# NewBee.net
KiCad netlist of a schematic drawn in Altium Designer
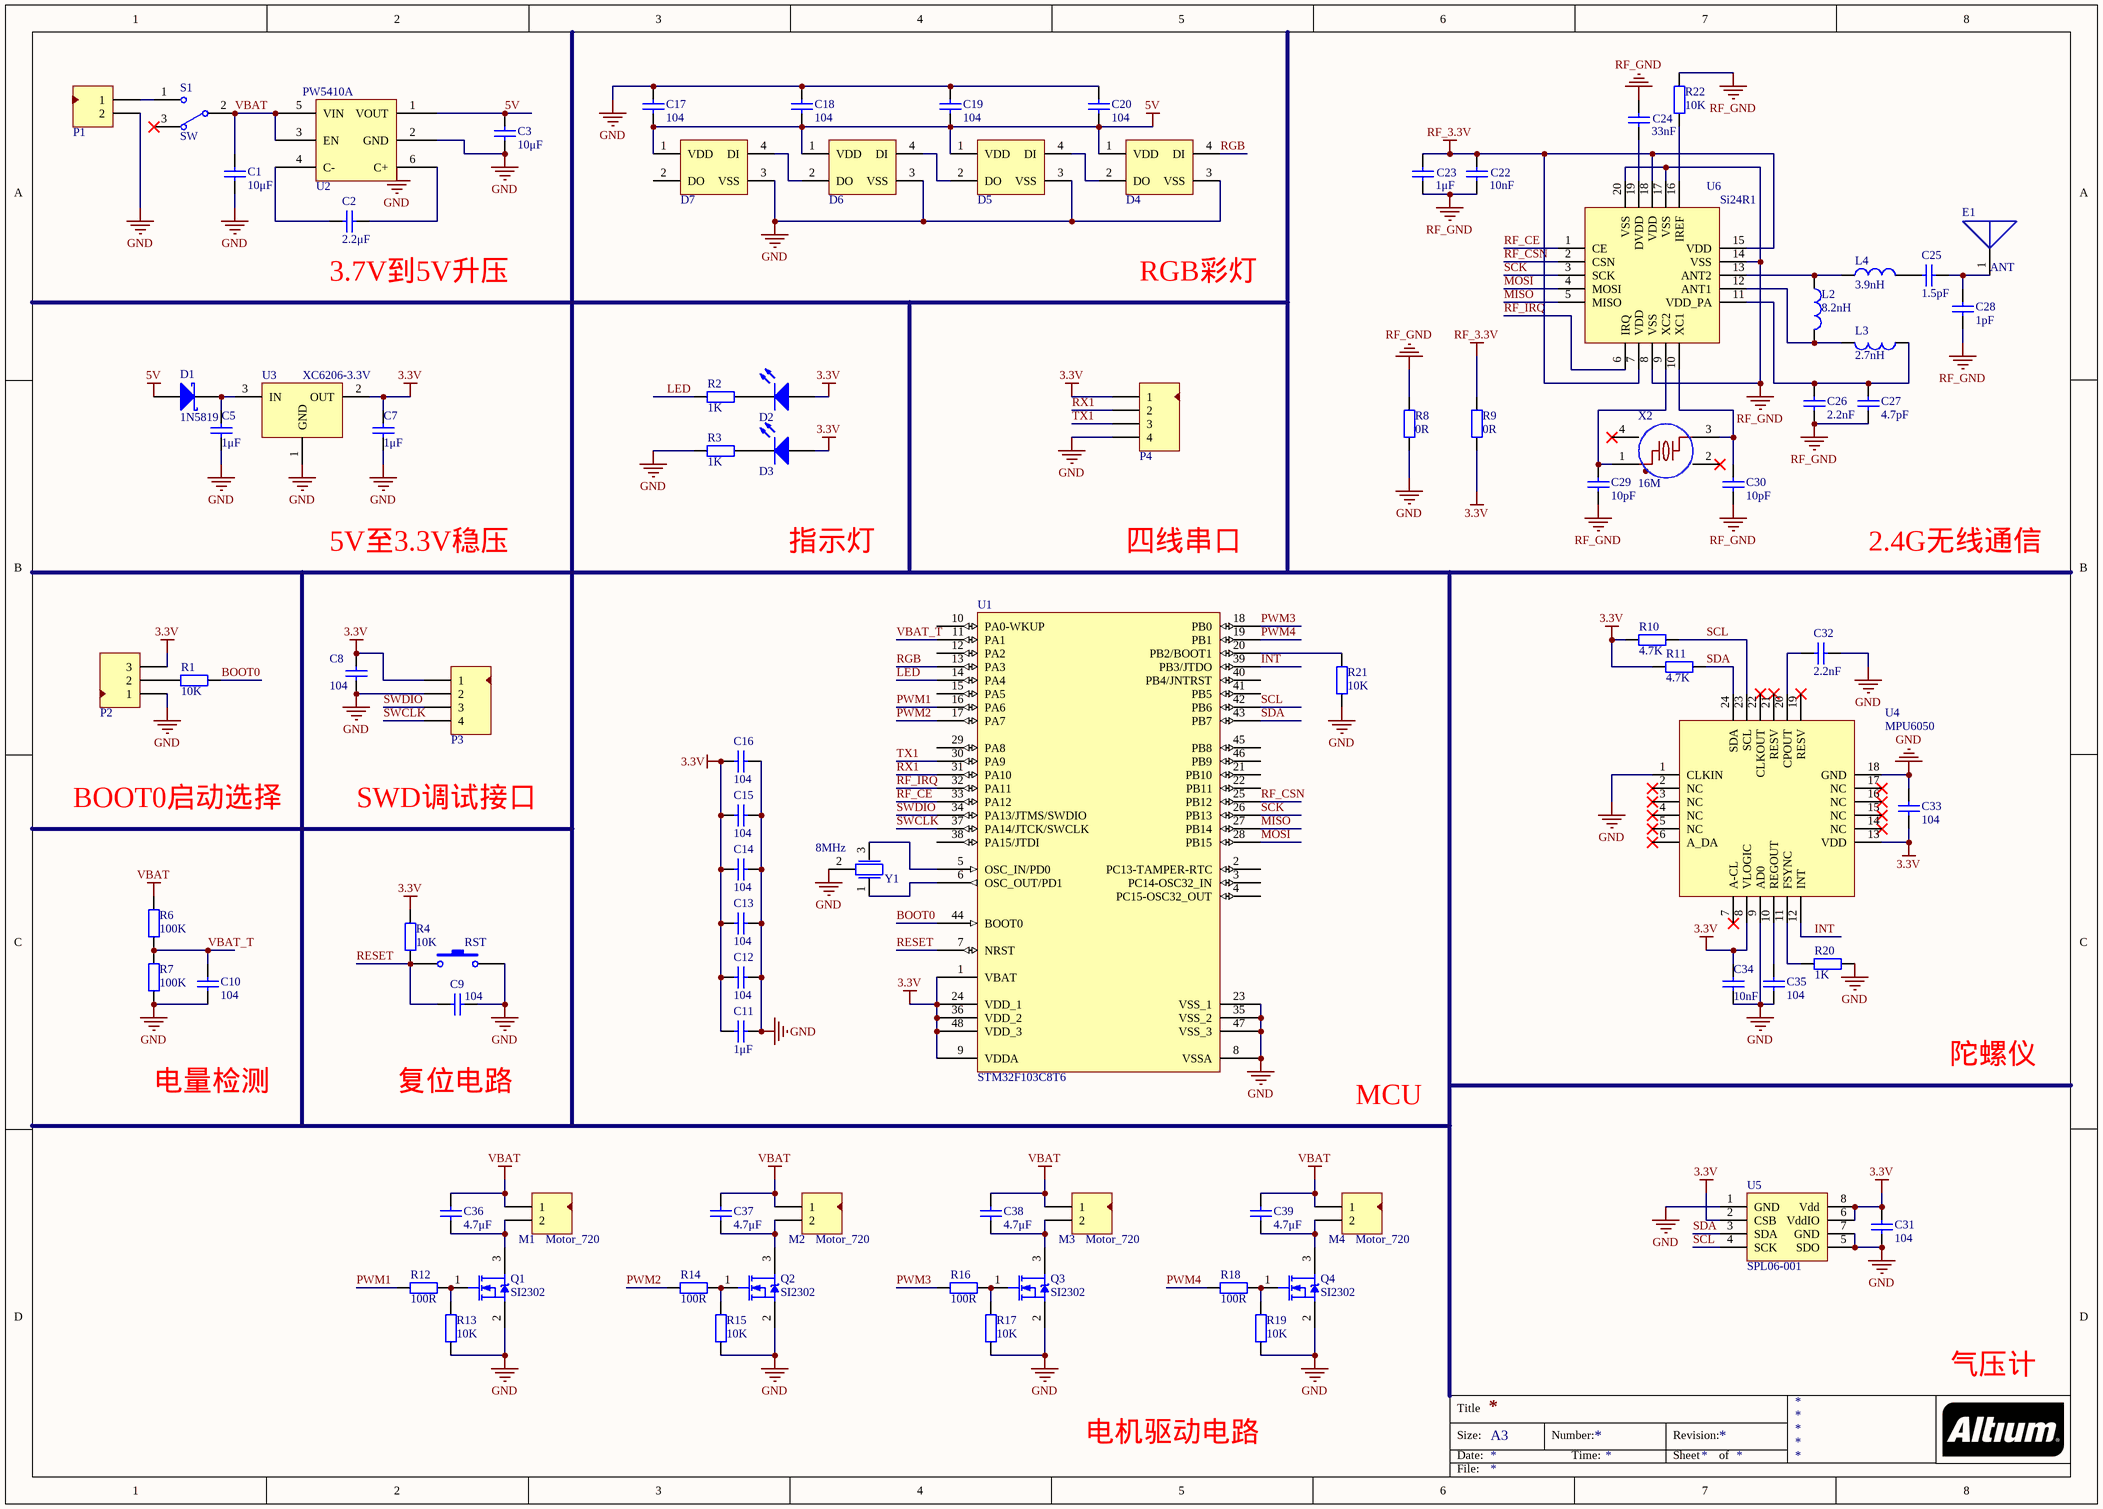
[diagram p0: NewBee.SchDoc]

(export (version "E")
  (design (tool "Eeschema 10.0.6"))
  (components
    (comp (ref "C1")
      (value "10μF")
      (footprint "C-0603")
      (description "贴片瓷片电容")
      (fields (field (name "PUBLISHER") "Altium Limited"))
      (libsource (lib "ChunLee") (part "Cap-S"))
    )
    (comp (ref "C2")
      (value "2.2μF")
      (footprint "C-0603")
      (description "贴片瓷片电容")
      (fields (field (name "PUBLISHER") "Altium Limited"))
      (libsource (lib "ChunLee") (part "Cap-S"))
    )
    (comp (ref "C3")
      (value "10μF")
      (footprint "C-0603")
      (description "贴片瓷片电容")
      (fields (field (name "PUBLISHER") "Altium Limited"))
      (libsource (lib "ChunLee") (part "Cap-S"))
    )
    (comp (ref "C5")
      (value "1μF")
      (footprint "C-0603")
      (description "贴片瓷片电容")
      (fields (field (name "PUBLISHER") "Altium Limited"))
      (libsource (lib "ChunLee") (part "Cap-S"))
    )
    (comp (ref "C7")
      (value "1μF")
      (footprint "C-0603")
      (description "贴片瓷片电容")
      (fields (field (name "PUBLISHER") "Altium Limited"))
      (libsource (lib "ChunLee") (part "Cap-S"))
    )
    (comp (ref "C8")
      (value "104")
      (footprint "C-0603")
      (description "贴片瓷片电容")
      (fields (field (name "PUBLISHER") "Altium Limited"))
      (libsource (lib "ChunLee") (part "Cap-S"))
    )
    (comp (ref "C9")
      (value "104")
      (footprint "C-0603")
      (description "贴片瓷片电容")
      (fields (field (name "PUBLISHER") "Altium Limited"))
      (libsource (lib "ChunLee") (part "Cap-S"))
    )
    (comp (ref "C10")
      (value "104")
      (footprint "C-0603")
      (description "贴片瓷片电容")
      (fields (field (name "PUBLISHER") "Altium Limited"))
      (libsource (lib "ChunLee") (part "Cap-S"))
    )
    (comp (ref "C11")
      (value "1μF")
      (footprint "C-0603")
      (description "贴片瓷片电容")
      (fields (field (name "PUBLISHER") "Altium Limited"))
      (libsource (lib "ChunLee") (part "Cap-S"))
    )
    (comp (ref "C12")
      (value "104")
      (footprint "C-0603")
      (description "贴片瓷片电容")
      (fields (field (name "PUBLISHER") "Altium Limited"))
      (libsource (lib "ChunLee") (part "Cap-S"))
    )
    (comp (ref "C13")
      (value "104")
      (footprint "C-0603")
      (description "贴片瓷片电容")
      (fields (field (name "PUBLISHER") "Altium Limited"))
      (libsource (lib "ChunLee") (part "Cap-S"))
    )
    (comp (ref "C14")
      (value "104")
      (footprint "C-0603")
      (description "贴片瓷片电容")
      (fields (field (name "PUBLISHER") "Altium Limited"))
      (libsource (lib "ChunLee") (part "Cap-S"))
    )
    (comp (ref "C15")
      (value "104")
      (footprint "C-0603")
      (description "贴片瓷片电容")
      (fields (field (name "PUBLISHER") "Altium Limited"))
      (libsource (lib "ChunLee") (part "Cap-S"))
    )
    (comp (ref "C16")
      (value "104")
      (footprint "C-0603")
      (description "贴片瓷片电容")
      (fields (field (name "PUBLISHER") "Altium Limited"))
      (libsource (lib "ChunLee") (part "Cap-S"))
    )
    (comp (ref "C17")
      (value "104")
      (footprint "C-0603")
      (description "贴片瓷片电容")
      (fields (field (name "PUBLISHER") "Altium Limited"))
      (libsource (lib "ChunLee") (part "Cap-S"))
    )
    (comp (ref "C18")
      (value "104")
      (footprint "C-0603")
      (description "贴片瓷片电容")
      (fields (field (name "PUBLISHER") "Altium Limited"))
      (libsource (lib "ChunLee") (part "Cap-S"))
    )
    (comp (ref "C19")
      (value "104")
      (footprint "C-0603")
      (description "贴片瓷片电容")
      (fields (field (name "PUBLISHER") "Altium Limited"))
      (libsource (lib "ChunLee") (part "Cap-S"))
    )
    (comp (ref "C20")
      (value "104")
      (footprint "C-0603")
      (description "贴片瓷片电容")
      (fields (field (name "PUBLISHER") "Altium Limited"))
      (libsource (lib "ChunLee") (part "Cap-S"))
    )
    (comp (ref "C22")
      (value "10nF")
      (footprint "C-0603")
      (description "贴片瓷片电容")
      (fields (field (name "PUBLISHER") "Altium Limited"))
      (libsource (lib "ChunLee") (part "Cap-S"))
    )
    (comp (ref "C23")
      (value "1μF")
      (footprint "C-0603")
      (description "贴片瓷片电容")
      (fields (field (name "PUBLISHER") "Altium Limited"))
      (libsource (lib "ChunLee") (part "Cap-S"))
    )
    (comp (ref "C24")
      (value "33nF")
      (footprint "C-0603")
      (description "贴片瓷片电容")
      (fields (field (name "PUBLISHER") "Altium Limited"))
      (libsource (lib "ChunLee") (part "Cap-S"))
    )
    (comp (ref "C25")
      (value "1.5pF")
      (footprint "C-0603")
      (description "贴片瓷片电容")
      (fields (field (name "PUBLISHER") "Altium Limited"))
      (libsource (lib "ChunLee") (part "Cap-S"))
    )
    (comp (ref "C26")
      (value "2.2nF")
      (footprint "C-0603")
      (description "贴片瓷片电容")
      (fields (field (name "PUBLISHER") "Altium Limited"))
      (libsource (lib "ChunLee") (part "Cap-S"))
    )
    (comp (ref "C27")
      (value "4.7pF")
      (footprint "C-0603")
      (description "贴片瓷片电容")
      (fields (field (name "PUBLISHER") "Altium Limited"))
      (libsource (lib "ChunLee") (part "Cap-S"))
    )
    (comp (ref "C28")
      (value "1pF")
      (footprint "C-0603")
      (description "贴片瓷片电容")
      (fields (field (name "PUBLISHER") "Altium Limited"))
      (libsource (lib "ChunLee") (part "Cap-S"))
    )
    (comp (ref "C29")
      (value "10pF")
      (footprint "C-0603")
      (description "贴片瓷片电容")
      (fields (field (name "PUBLISHER") "Altium Limited"))
      (libsource (lib "ChunLee") (part "Cap-S"))
    )
    (comp (ref "C30")
      (value "10pF")
      (footprint "C-0603")
      (description "贴片瓷片电容")
      (fields (field (name "PUBLISHER") "Altium Limited"))
      (libsource (lib "ChunLee") (part "Cap-S"))
    )
    (comp (ref "C31")
      (value "104")
      (footprint "C-0603")
      (description "贴片瓷片电容")
      (fields (field (name "PUBLISHER") "Altium Limited"))
      (libsource (lib "ChunLee") (part "Cap-S"))
    )
    (comp (ref "C32")
      (value "2.2nF")
      (footprint "C-0603")
      (description "贴片瓷片电容")
      (fields (field (name "PUBLISHER") "Altium Limited"))
      (libsource (lib "ChunLee") (part "Cap-S"))
    )
    (comp (ref "C33")
      (value "104")
      (footprint "C-0603")
      (description "贴片瓷片电容")
      (fields (field (name "PUBLISHER") "Altium Limited"))
      (libsource (lib "ChunLee") (part "Cap-S"))
    )
    (comp (ref "C34")
      (value "10nF")
      (footprint "C-0603")
      (description "贴片瓷片电容")
      (fields (field (name "PUBLISHER") "Altium Limited"))
      (libsource (lib "ChunLee") (part "Cap-S"))
    )
    (comp (ref "C35")
      (value "104")
      (footprint "C-0603")
      (description "贴片瓷片电容")
      (fields (field (name "PUBLISHER") "Altium Limited"))
      (libsource (lib "ChunLee") (part "Cap-S"))
    )
    (comp (ref "C36")
      (value "4.7μF")
      (footprint "C-0603")
      (description "贴片瓷片电容")
      (fields (field (name "PUBLISHER") "Altium Limited"))
      (libsource (lib "ChunLee") (part "Cap-S"))
    )
    (comp (ref "C37")
      (value "4.7μF")
      (footprint "C-0603")
      (description "贴片瓷片电容")
      (fields (field (name "PUBLISHER") "Altium Limited"))
      (libsource (lib "ChunLee") (part "Cap-S"))
    )
    (comp (ref "C38")
      (value "4.7μF")
      (footprint "C-0603")
      (description "贴片瓷片电容")
      (fields (field (name "PUBLISHER") "Altium Limited"))
      (libsource (lib "ChunLee") (part "Cap-S"))
    )
    (comp (ref "C39")
      (value "4.7μF")
      (footprint "C-0603")
      (description "贴片瓷片电容")
      (fields (field (name "PUBLISHER") "Altium Limited"))
      (libsource (lib "ChunLee") (part "Cap-S"))
    )
    (comp (ref "D1")
      (value "1N5819")
      (footprint "SOD-323_L1.6-W1.3-LS2.7-RD")
      (description "肖特基二极管")
      (fields (field (name "TYPE") "1N5819") (field (name "PUBLISHER") "Altium Limited"))
      (libsource (lib "ChunLee") (part "Diode-Schottky"))
    )
    (comp (ref "D2")
      (value "LED0")
      (footprint "LED-0805")
      (description "发光二极管")
      (fields (field (name "PUBLISHER") "Altium Limited"))
      (libsource (lib "ChunLee") (part "LED0"))
    )
    (comp (ref "D3")
      (value "LED0")
      (footprint "LED-0805")
      (description "发光二极管")
      (fields (field (name "PUBLISHER") "Altium Limited"))
      (libsource (lib "ChunLee") (part "LED0"))
    )
    (comp (ref "D4")
      (value "WS2812B")
      (footprint "SMD-5050-4")
      (description "WS2812B 4脚RGB全彩LED")
      (libsource (lib "ChunLee") (part "WS2812B"))
    )
    (comp (ref "D5")
      (value "WS2812B")
      (footprint "SMD-5050-4")
      (description "WS2812B 4脚RGB全彩LED")
      (libsource (lib "ChunLee") (part "WS2812B"))
    )
    (comp (ref "D6")
      (value "WS2812B")
      (footprint "SMD-5050-4")
      (description "WS2812B 4脚RGB全彩LED")
      (libsource (lib "ChunLee") (part "WS2812B"))
    )
    (comp (ref "D7")
      (value "WS2812B")
      (footprint "SMD-5050-4")
      (description "WS2812B 4脚RGB全彩LED")
      (libsource (lib "ChunLee") (part "WS2812B"))
    )
    (comp (ref "E1")
      (value "ANT")
      (footprint "NewBee_PcbLib:AN3216")
      (description "2.4G Antenna")
      (fields (field (name "PUBLISHER") "mazhongwei"))
      (libsource (lib "NewBee_Schlib") (part "ANT"))
    )
    (comp (ref "L2")
      (value "8.2nH")
      (footprint "0603-1")
      (description "电感")
      (fields (field (name "Comment") "Inductor") (field (name "PUBLISHER") "Altium Limited"))
      (libsource (lib "ChunLee") (part "Inductor"))
    )
    (comp (ref "L3")
      (value "2.7nH")
      (footprint "0603-1")
      (description "电感")
      (fields (field (name "Comment") "Inductor") (field (name "PUBLISHER") "Altium Limited"))
      (libsource (lib "ChunLee") (part "Inductor"))
    )
    (comp (ref "L4")
      (value "3.9nH")
      (footprint "0603-1")
      (description "电感")
      (fields (field (name "Comment") "Inductor") (field (name "PUBLISHER") "Altium Limited"))
      (libsource (lib "ChunLee") (part "Inductor"))
    )
    (comp (ref "M1")
      (value "Motor_720")
      (footprint "PH2.0-2P-TH")
      (description "接插件")
      (fields (field (name "PUBLISHER") "Altium Limited"))
      (libsource (lib "HDR_ChunLee") (part "Header 2"))
    )
    (comp (ref "M2")
      (value "Motor_720")
      (footprint "PH2.0-2P-TH")
      (description "接插件")
      (fields (field (name "PUBLISHER") "Altium Limited"))
      (libsource (lib "HDR_ChunLee") (part "Header 2"))
    )
    (comp (ref "M3")
      (value "Motor_720")
      (footprint "PH2.0-2P-TH")
      (description "接插件")
      (fields (field (name "PUBLISHER") "Altium Limited"))
      (libsource (lib "HDR_ChunLee") (part "Header 2"))
    )
    (comp (ref "M4")
      (value "Motor_720")
      (footprint "PH2.0-2P-TH")
      (description "接插件")
      (fields (field (name "PUBLISHER") "Altium Limited"))
      (libsource (lib "HDR_ChunLee") (part "Header 2"))
    )
    (comp (ref "P1")
      (value "Header 2")
      (footprint "PH1.25-2P-SMD-WT")
      (description "接插件")
      (fields (field (name "PUBLISHER") "Altium Limited"))
      (libsource (lib "") (part "Header 2_1"))
    )
    (comp (ref "P2")
      (value "Header 3")
      (footprint "HDR3X1-2.54")
      (description "接插件")
      (fields (field (name "PUBLISHER") "Altium Limited"))
      (libsource (lib "HDR_ChunLee") (part "Header 3"))
    )
    (comp (ref "P3")
      (value "Header 4")
      (footprint "HDR4X1-2.54")
      (description "接插件")
      (fields (field (name "PUBLISHER") "Altium Limited"))
      (libsource (lib "HDR_ChunLee") (part "Header 4"))
    )
    (comp (ref "P4")
      (value "Header 4")
      (footprint "HDR4X1-2.54")
      (description "接插件")
      (fields (field (name "PUBLISHER") "Altium Limited"))
      (libsource (lib "HDR_ChunLee") (part "Header 4"))
    )
    (comp (ref "Q1")
      (value "SI2302")
      (footprint "SOT23-3")
      (description "N沟道贴片")
      (fields (field (name "PUBLISHER") "Altium Limited"))
      (libsource (lib "ChunLee") (part "SI2302"))
    )
    (comp (ref "Q2")
      (value "SI2302")
      (footprint "SOT23-3")
      (description "N沟道贴片")
      (fields (field (name "PUBLISHER") "Altium Limited"))
      (libsource (lib "ChunLee") (part "SI2302"))
    )
    (comp (ref "Q3")
      (value "SI2302")
      (footprint "SOT23-3")
      (description "N沟道贴片")
      (fields (field (name "PUBLISHER") "Altium Limited"))
      (libsource (lib "ChunLee") (part "SI2302"))
    )
    (comp (ref "Q4")
      (value "SI2302")
      (footprint "SOT23-3")
      (description "N沟道贴片")
      (fields (field (name "PUBLISHER") "Altium Limited"))
      (libsource (lib "ChunLee") (part "SI2302"))
    )
    (comp (ref "R1")
      (value "10K")
      (footprint "0603-1")
      (description "贴片电阻")
      (fields (field (name "PUBLISHER") "Altium Limited"))
      (libsource (lib "ChunLee") (part "Res1"))
    )
    (comp (ref "R2")
      (value "1K")
      (footprint "0603-1")
      (description "贴片电阻")
      (fields (field (name "PUBLISHER") "Altium Limited"))
      (libsource (lib "") (part "Res1_1"))
    )
    (comp (ref "R3")
      (value "1K")
      (footprint "0603-1")
      (description "贴片电阻")
      (fields (field (name "PUBLISHER") "Altium Limited"))
      (libsource (lib "") (part "Res1_1"))
    )
    (comp (ref "R4")
      (value "10K")
      (footprint "0603-1")
      (description "贴片电阻")
      (fields (field (name "PUBLISHER") "Altium Limited"))
      (libsource (lib "") (part "Res1_3"))
    )
    (comp (ref "R6")
      (value "100K")
      (footprint "0603-1")
      (description "贴片电阻")
      (fields (field (name "PUBLISHER") "Altium Limited"))
      (libsource (lib "") (part "Res1_2"))
    )
    (comp (ref "R7")
      (value "100K")
      (footprint "0603-1")
      (description "贴片电阻")
      (fields (field (name "PUBLISHER") "Altium Limited"))
      (libsource (lib "") (part "Res1_2"))
    )
    (comp (ref "R8")
      (value "0R")
      (footprint "0603-1")
      (description "贴片电阻")
      (fields (field (name "PUBLISHER") "Altium Limited"))
      (libsource (lib "") (part "Res1_2"))
    )
    (comp (ref "R9")
      (value "0R")
      (footprint "0603-1")
      (description "贴片电阻")
      (fields (field (name "PUBLISHER") "Altium Limited"))
      (libsource (lib "") (part "Res1_2"))
    )
    (comp (ref "R10")
      (value "4.7K")
      (footprint "0603-1")
      (description "贴片电阻")
      (fields (field (name "PUBLISHER") "Altium Limited"))
      (libsource (lib "") (part "Res1_1"))
    )
    (comp (ref "R11")
      (value "4.7K")
      (footprint "0603-1")
      (description "贴片电阻")
      (fields (field (name "PUBLISHER") "Altium Limited"))
      (libsource (lib "") (part "Res1_1"))
    )
    (comp (ref "R12")
      (value "100R")
      (footprint "0603-1")
      (description "贴片电阻")
      (fields (field (name "PUBLISHER") "Altium Limited"))
      (libsource (lib "") (part "Res1_1"))
    )
    (comp (ref "R13")
      (value "10K")
      (footprint "0603-1")
      (description "贴片电阻")
      (fields (field (name "PUBLISHER") "Altium Limited"))
      (libsource (lib "") (part "Res1_3"))
    )
    (comp (ref "R14")
      (value "100R")
      (footprint "0603-1")
      (description "贴片电阻")
      (fields (field (name "PUBLISHER") "Altium Limited"))
      (libsource (lib "") (part "Res1_1"))
    )
    (comp (ref "R15")
      (value "10K")
      (footprint "0603-1")
      (description "贴片电阻")
      (fields (field (name "PUBLISHER") "Altium Limited"))
      (libsource (lib "") (part "Res1_3"))
    )
    (comp (ref "R16")
      (value "100R")
      (footprint "0603-1")
      (description "贴片电阻")
      (fields (field (name "PUBLISHER") "Altium Limited"))
      (libsource (lib "") (part "Res1_1"))
    )
    (comp (ref "R17")
      (value "10K")
      (footprint "0603-1")
      (description "贴片电阻")
      (fields (field (name "PUBLISHER") "Altium Limited"))
      (libsource (lib "") (part "Res1_3"))
    )
    (comp (ref "R18")
      (value "100R")
      (footprint "0603-1")
      (description "贴片电阻")
      (fields (field (name "PUBLISHER") "Altium Limited"))
      (libsource (lib "") (part "Res1_1"))
    )
    (comp (ref "R19")
      (value "10K")
      (footprint "0603-1")
      (description "贴片电阻")
      (fields (field (name "PUBLISHER") "Altium Limited"))
      (libsource (lib "") (part "Res1_3"))
    )
    (comp (ref "R20")
      (value "1K")
      (footprint "0603-1")
      (description "贴片电阻")
      (fields (field (name "PUBLISHER") "Altium Limited"))
      (libsource (lib "ChunLee") (part "Res1"))
    )
    (comp (ref "R21")
      (value "10K")
      (footprint "0603-1")
      (description "贴片电阻")
      (fields (field (name "PUBLISHER") "Altium Limited"))
      (libsource (lib "") (part "Res1_2"))
    )
    (comp (ref "R22")
      (value "10K")
      (footprint "0603-1")
      (description "贴片电阻")
      (fields (field (name "PUBLISHER") "Altium Limited"))
      (libsource (lib "") (part "Res1_2"))
    )
    (comp (ref "RST")
      (value "SW-PB")
      (footprint "SW-SMD_L4.0-W3.0-P4.8-LS5.0-L")
      (description "微动开关")
      (fields (field (name "PUBLISHER") "Altium Limited"))
      (libsource (lib "ChunLee") (part "SW-PB"))
    )
    (comp (ref "S1")
      (value "SW")
      (footprint "SW-SMD_DEALON_MK-12D04-G2")
      (description "开关")
      (fields (field (name "PUBLISHER") "Altium Limited"))
      (libsource (lib "ChunLee") (part "SW-SPDT"))
    )
    (comp (ref "U1")
      (value "STM32F103C8T6")
      (footprint "LQFP-48")
      (description "STM32F103, 48引脚, 64Kb Flash, 20Kb SRAM")
      (fields (field (name "PUBLISHER") "Altium Limited"))
      (libsource (lib "ChunLee") (part "STM32F103C8T6"))
    )
    (comp (ref "U2")
      (value "PW5410A")
      (footprint "SOT23-6")
      (description "5V/3.3V升压芯片")
      (libsource (lib "ChunLee") (part "PW5410A/B"))
    )
    (comp (ref "U3")
      (value "XC6206-3.3V")
      (footprint "SOT23-3")
      (description "稳压芯片")
      (libsource (lib "ChunLee") (part "XC6206"))
    )
    (comp (ref "U4") (value "MPU6050") (footprint "QFN-24") (libsource (lib "ChunLee") (part "MPU6050")))
    (comp (ref "U5")
      (value "SPL06-001")
      (footprint "SENSOR-SMD_SPL06-001")
      (description "气压计")
      (fields (field (name "PUBLISHER") "mazhongwei"))
      (libsource (lib "NewBee_Schlib") (part "FBM320"))
    )
    (comp (ref "U6") (value "Si24R1") (footprint "QFN20") (libsource (lib "NewBee_Schlib") (part "nRF24L01")))
    (comp (ref "X2")
      (value "16M")
      (footprint "X-SMD_4P-L3.2-W2.5-BL")
      (libsource (lib "ChunLee") (part "XTAL-4PIN"))
    )
    (comp (ref "Y1")
      (value "8MHz")
      (footprint "OSC-SMD_3P-L3.2-W1.3-P1.20-L")
      (description "贴片晶振")
      (libsource (lib "ChunLee") (part "XTAL-3PIN"))
    )
  )
  (nets
    (net (code "1") (name "/BOOT0") (class "Default")
      (node (ref "R1") (pin "1") (pinfunction "1_1") (pintype "passive"))
      (node (ref "U1") (pin "44") (pinfunction "BOOT0_44") (pintype "input"))
    )
    (net (code "2") (name "/INT") (class "Default")
      (node (ref "U1") (pin "39") (pinfunction "PB3/JTDO_39") (pintype "bidirectional"))
      (node (ref "U4") (pin "12") (pinfunction "INT_12") (pintype "passive"))
    )
    (net (code "3") (name "/LED") (class "Default")
      (node (ref "R2") (pin "1") (pinfunction "1_1") (pintype "passive"))
      (node (ref "U1") (pin "14") (pinfunction "PA4_14") (pintype "bidirectional"))
    )
    (net (code "4") (name "/MISO") (class "Default")
      (node (ref "U1") (pin "27") (pinfunction "PB14_27") (pintype "bidirectional"))
      (node (ref "U6") (pin "5") (pinfunction "MISO_5") (pintype "passive"))
    )
    (net (code "5") (name "/MOSI") (class "Default")
      (node (ref "U1") (pin "28") (pinfunction "PB15_28") (pintype "bidirectional"))
      (node (ref "U6") (pin "4") (pinfunction "MOSI_4") (pintype "passive"))
    )
    (net (code "6") (name "/PWM1") (class "Default")
      (node (ref "R12") (pin "1") (pinfunction "1_1") (pintype "passive"))
      (node (ref "U1") (pin "16") (pinfunction "PA6_16") (pintype "bidirectional"))
    )
    (net (code "7") (name "/PWM2") (class "Default")
      (node (ref "R14") (pin "1") (pinfunction "1_1") (pintype "passive"))
      (node (ref "U1") (pin "17") (pinfunction "PA7_17") (pintype "bidirectional"))
    )
    (net (code "8") (name "/PWM3") (class "Default")
      (node (ref "R16") (pin "1") (pinfunction "1_1") (pintype "passive"))
      (node (ref "U1") (pin "18") (pinfunction "PB0_18") (pintype "bidirectional"))
    )
    (net (code "9") (name "/PWM4") (class "Default")
      (node (ref "R18") (pin "1") (pinfunction "1_1") (pintype "passive"))
      (node (ref "U1") (pin "19") (pinfunction "PB1_19") (pintype "bidirectional"))
    )
    (net (code "10") (name "/RESET") (class "Default")
      (node (ref "C9") (pin "1") (pinfunction "1_1") (pintype "passive"))
      (node (ref "R4") (pin "1") (pinfunction "1_1") (pintype "passive"))
      (node (ref "RST") (pin "1") (pinfunction "1_1") (pintype "passive"))
      (node (ref "U1") (pin "7") (pinfunction "NRST_7") (pintype "bidirectional"))
    )
    (net (code "11") (name "/RF_CE") (class "Default")
      (node (ref "U1") (pin "33") (pinfunction "PA12_33") (pintype "bidirectional"))
      (node (ref "U6") (pin "1") (pinfunction "CE_1") (pintype "passive"))
    )
    (net (code "12") (name "/RF_CSN") (class "Default")
      (node (ref "U1") (pin "25") (pinfunction "PB12_25") (pintype "bidirectional"))
      (node (ref "U6") (pin "2") (pinfunction "CSN_2") (pintype "passive"))
    )
    (net (code "13") (name "/RF_IRQ") (class "Default")
      (node (ref "U1") (pin "32") (pinfunction "PA11_32") (pintype "bidirectional"))
      (node (ref "U6") (pin "6") (pinfunction "IRQ_6") (pintype "passive"))
    )
    (net (code "14") (name "/RGB") (class "Default")
      (node (ref "D4") (pin "4") (pinfunction "DI_4") (pintype "passive"))
      (node (ref "U1") (pin "13") (pinfunction "PA3_13") (pintype "bidirectional"))
    )
    (net (code "15") (name "/RX1") (class "Default")
      (node (ref "P4") (pin "2") (pinfunction "2_2") (pintype "passive"))
      (node (ref "U1") (pin "31") (pinfunction "PA10_31") (pintype "bidirectional"))
    )
    (net (code "16") (name "/SCK") (class "Default")
      (node (ref "U1") (pin "26") (pinfunction "PB13_26") (pintype "bidirectional"))
      (node (ref "U6") (pin "3") (pinfunction "SCK_3") (pintype "passive"))
    )
    (net (code "17") (name "/SCL") (class "Default")
      (node (ref "R10") (pin "2") (pinfunction "2_2") (pintype "passive"))
      (node (ref "U1") (pin "42") (pinfunction "PB6_42") (pintype "bidirectional"))
      (node (ref "U4") (pin "23") (pinfunction "SCL_23") (pintype "passive"))
      (node (ref "U5") (pin "4") (pinfunction "SCK_4") (pintype "passive"))
    )
    (net (code "18") (name "/SDA") (class "Default")
      (node (ref "R11") (pin "2") (pinfunction "2_2") (pintype "passive"))
      (node (ref "U1") (pin "43") (pinfunction "PB7_43") (pintype "bidirectional"))
      (node (ref "U4") (pin "24") (pinfunction "SDA_24") (pintype "passive"))
      (node (ref "U5") (pin "3") (pinfunction "SDA_3") (pintype "passive"))
    )
    (net (code "19") (name "/SWCLK") (class "Default")
      (node (ref "P3") (pin "4") (pinfunction "4_4") (pintype "passive"))
      (node (ref "U1") (pin "37") (pinfunction "PA14/JTCK/SWCLK_37") (pintype "bidirectional"))
    )
    (net (code "20") (name "/SWDIO") (class "Default")
      (node (ref "P3") (pin "3") (pinfunction "3_3") (pintype "passive"))
      (node (ref "U1") (pin "34") (pinfunction "PA13/JTMS/SWDIO_34") (pintype "bidirectional"))
    )
    (net (code "21") (name "/TX1") (class "Default")
      (node (ref "P4") (pin "3") (pinfunction "3_3") (pintype "passive"))
      (node (ref "U1") (pin "30") (pinfunction "PA9_30") (pintype "bidirectional"))
    )
    (net (code "22") (name "/VBAT_T") (class "Default")
      (node (ref "C10") (pin "2") (pinfunction "2_2") (pintype "passive"))
      (node (ref "R6") (pin "2") (pinfunction "2_2") (pintype "passive"))
      (node (ref "R7") (pin "1") (pinfunction "1_1") (pintype "passive"))
      (node (ref "U1") (pin "11") (pinfunction "PA1_11") (pintype "bidirectional"))
    )
    (net (code "23") (name "3.3V") (class "Default")
      (node (ref "C11") (pin "2") (pinfunction "2_2") (pintype "passive"))
      (node (ref "C12") (pin "2") (pinfunction "2_2") (pintype "passive"))
      (node (ref "C13") (pin "2") (pinfunction "2_2") (pintype "passive"))
      (node (ref "C14") (pin "1") (pinfunction "1_1") (pintype "passive"))
      (node (ref "C15") (pin "2") (pinfunction "2_2") (pintype "passive"))
      (node (ref "C16") (pin "2") (pinfunction "2_2") (pintype "passive"))
      (node (ref "C31") (pin "2") (pinfunction "2_2") (pintype "passive"))
      (node (ref "C33") (pin "2") (pinfunction "2_2") (pintype "passive"))
      (node (ref "C34") (pin "2") (pinfunction "2_2") (pintype "passive"))
      (node (ref "C7") (pin "1") (pinfunction "1_1") (pintype "passive"))
      (node (ref "C8") (pin "1") (pinfunction "1_1") (pintype "passive"))
      (node (ref "D2") (pin "1") (pinfunction "A_1") (pintype "passive"))
      (node (ref "D3") (pin "1") (pinfunction "A_1") (pintype "passive"))
      (node (ref "P2") (pin "3") (pinfunction "3_3") (pintype "passive"))
      (node (ref "P3") (pin "1") (pinfunction "1_1") (pintype "passive"))
      (node (ref "P4") (pin "1") (pinfunction "1_1") (pintype "passive"))
      (node (ref "R10") (pin "1") (pinfunction "1_1") (pintype "passive"))
      (node (ref "R11") (pin "1") (pinfunction "1_1") (pintype "passive"))
      (node (ref "R4") (pin "2") (pinfunction "2_2") (pintype "passive"))
      (node (ref "R9") (pin "2") (pinfunction "2_2") (pintype "passive"))
      (node (ref "U1") (pin "1") (pinfunction "VBAT_1") (pintype "power_in"))
      (node (ref "U1") (pin "24") (pinfunction "VDD_1_24") (pintype "power_in"))
      (node (ref "U1") (pin "36") (pinfunction "VDD_2_36") (pintype "power_in"))
      (node (ref "U1") (pin "48") (pinfunction "VDD_3_48") (pintype "power_in"))
      (node (ref "U1") (pin "9") (pinfunction "VDDA_9") (pintype "power_in"))
      (node (ref "U3") (pin "2") (pinfunction "OUT_2") (pintype "passive"))
      (node (ref "U4") (pin "13") (pinfunction "VDD_13") (pintype "passive"))
      (node (ref "U4") (pin "8") (pinfunction "VLOGIC_8") (pintype "passive"))
      (node (ref "U5") (pin "2") (pinfunction "CSB_2") (pintype "passive"))
      (node (ref "U5") (pin "6") (pinfunction "VddIO_6") (pintype "passive"))
      (node (ref "U5") (pin "8") (pinfunction "Vdd_8") (pintype "passive"))
    )
    (net (code "24") (name "5V") (class "Default")
      (node (ref "C17") (pin "1") (pinfunction "1_1") (pintype "passive"))
      (node (ref "C18") (pin "1") (pinfunction "1_1") (pintype "passive"))
      (node (ref "C19") (pin "1") (pinfunction "1_1") (pintype "passive"))
      (node (ref "C20") (pin "1") (pinfunction "1_1") (pintype "passive"))
      (node (ref "C3") (pin "2") (pinfunction "2_2") (pintype "passive"))
      (node (ref "D1") (pin "1") (pinfunction "A_1") (pintype "passive"))
      (node (ref "D4") (pin "1") (pinfunction "VDD_1") (pintype "passive"))
      (node (ref "D5") (pin "1") (pinfunction "VDD_1") (pintype "passive"))
      (node (ref "D6") (pin "1") (pinfunction "VDD_1") (pintype "passive"))
      (node (ref "D7") (pin "1") (pinfunction "VDD_1") (pintype "passive"))
      (node (ref "U2") (pin "1") (pinfunction "VOUT_1") (pintype "passive"))
    )
    (net (code "25") (name "GND") (class "Default")
      (node (ref "C1") (pin "1") (pinfunction "1_1") (pintype "passive"))
      (node (ref "C10") (pin "1") (pinfunction "1_1") (pintype "passive"))
      (node (ref "C11") (pin "1") (pinfunction "1_1") (pintype "passive"))
      (node (ref "C12") (pin "1") (pinfunction "1_1") (pintype "passive"))
      (node (ref "C13") (pin "1") (pinfunction "1_1") (pintype "passive"))
      (node (ref "C14") (pin "2") (pinfunction "2_2") (pintype "passive"))
      (node (ref "C15") (pin "1") (pinfunction "1_1") (pintype "passive"))
      (node (ref "C16") (pin "1") (pinfunction "1_1") (pintype "passive"))
      (node (ref "C17") (pin "2") (pinfunction "2_2") (pintype "passive"))
      (node (ref "C18") (pin "2") (pinfunction "2_2") (pintype "passive"))
      (node (ref "C19") (pin "2") (pinfunction "2_2") (pintype "passive"))
      (node (ref "C20") (pin "2") (pinfunction "2_2") (pintype "passive"))
      (node (ref "C3") (pin "1") (pinfunction "1_1") (pintype "passive"))
      (node (ref "C31") (pin "1") (pinfunction "1_1") (pintype "passive"))
      (node (ref "C32") (pin "1") (pinfunction "1_1") (pintype "passive"))
      (node (ref "C33") (pin "1") (pinfunction "1_1") (pintype "passive"))
      (node (ref "C34") (pin "1") (pinfunction "1_1") (pintype "passive"))
      (node (ref "C35") (pin "2") (pinfunction "2_2") (pintype "passive"))
      (node (ref "C5") (pin "2") (pinfunction "2_2") (pintype "passive"))
      (node (ref "C7") (pin "2") (pinfunction "2_2") (pintype "passive"))
      (node (ref "C8") (pin "2") (pinfunction "2_2") (pintype "passive"))
      (node (ref "C9") (pin "2") (pinfunction "2_2") (pintype "passive"))
      (node (ref "D4") (pin "3") (pinfunction "VSS_3") (pintype "passive"))
      (node (ref "D5") (pin "3") (pinfunction "VSS_3") (pintype "passive"))
      (node (ref "D6") (pin "3") (pinfunction "VSS_3") (pintype "passive"))
      (node (ref "D7") (pin "3") (pinfunction "VSS_3") (pintype "passive"))
      (node (ref "P1") (pin "2") (pinfunction "2_2") (pintype "passive"))
      (node (ref "P2") (pin "1") (pinfunction "1_1") (pintype "passive"))
      (node (ref "P3") (pin "2") (pinfunction "2_2") (pintype "passive"))
      (node (ref "P4") (pin "4") (pinfunction "4_4") (pintype "passive"))
      (node (ref "Q1") (pin "2") (pinfunction "S_2") (pintype "passive"))
      (node (ref "Q2") (pin "2") (pinfunction "S_2") (pintype "passive"))
      (node (ref "Q3") (pin "2") (pinfunction "S_2") (pintype "passive"))
      (node (ref "Q4") (pin "2") (pinfunction "S_2") (pintype "passive"))
      (node (ref "R13") (pin "1") (pinfunction "1_1") (pintype "passive"))
      (node (ref "R15") (pin "1") (pinfunction "1_1") (pintype "passive"))
      (node (ref "R17") (pin "1") (pinfunction "1_1") (pintype "passive"))
      (node (ref "R19") (pin "1") (pinfunction "1_1") (pintype "passive"))
      (node (ref "R20") (pin "1") (pinfunction "1_1") (pintype "passive"))
      (node (ref "R21") (pin "2") (pinfunction "2_2") (pintype "passive"))
      (node (ref "R3") (pin "1") (pinfunction "1_1") (pintype "passive"))
      (node (ref "R7") (pin "2") (pinfunction "2_2") (pintype "passive"))
      (node (ref "R8") (pin "2") (pinfunction "2_2") (pintype "passive"))
      (node (ref "RST") (pin "2") (pinfunction "2_2") (pintype "passive"))
      (node (ref "U1") (pin "23") (pinfunction "VSS_1_23") (pintype "power_in"))
      (node (ref "U1") (pin "35") (pinfunction "VSS_2_35") (pintype "power_in"))
      (node (ref "U1") (pin "47") (pinfunction "VSS_3_47") (pintype "power_in"))
      (node (ref "U1") (pin "8") (pinfunction "VSSA_8") (pintype "power_in"))
      (node (ref "U2") (pin "2") (pinfunction "GND_2") (pintype "passive"))
      (node (ref "U3") (pin "1") (pinfunction "GND_1") (pintype "passive"))
      (node (ref "U4") (pin "1") (pinfunction "CLKIN_1") (pintype "passive"))
      (node (ref "U4") (pin "18") (pinfunction "GND_18") (pintype "passive"))
      (node (ref "U4") (pin "9") (pinfunction "AD0_9") (pintype "passive"))
      (node (ref "U5") (pin "1") (pinfunction "GND_1") (pintype "passive"))
      (node (ref "U5") (pin "5") (pinfunction "SDO_5") (pintype "passive"))
      (node (ref "U5") (pin "7") (pinfunction "GND_7") (pintype "passive"))
      (node (ref "Y1") (pin "2") (pinfunction "2_2") (pintype "passive"))
    )
    (net (code "26") (name "Net-(C25-Pad1)") (class "Default")
      (node (ref "C25") (pin "1") (pinfunction "1_1") (pintype "passive"))
      (node (ref "C28") (pin "2") (pinfunction "2_2") (pintype "passive"))
      (node (ref "E1") (pin "1") (pinfunction "1_1") (pintype "passive"))
    )
    (net (code "27") (name "Net-(C25-Pad2)") (class "Default")
      (node (ref "C25") (pin "2") (pinfunction "2_2") (pintype "passive"))
      (node (ref "L4") (pin "2") (pinfunction "2_2") (pintype "passive"))
    )
    (net (code "28") (name "Net-(D1-K)") (class "Default")
      (node (ref "C5") (pin "1") (pinfunction "1_1") (pintype "passive"))
      (node (ref "D1") (pin "2") (pinfunction "K_2") (pintype "passive"))
      (node (ref "U3") (pin "3") (pinfunction "IN_3") (pintype "passive"))
    )
    (net (code "29") (name "Net-(D2-K)") (class "Default")
      (node (ref "D2") (pin "2") (pinfunction "K_2") (pintype "passive"))
      (node (ref "R2") (pin "2") (pinfunction "2_2") (pintype "passive"))
    )
    (net (code "30") (name "Net-(D3-K)") (class "Default")
      (node (ref "D3") (pin "2") (pinfunction "K_2") (pintype "passive"))
      (node (ref "R3") (pin "2") (pinfunction "2_2") (pintype "passive"))
    )
    (net (code "31") (name "Net-(D4-DO)") (class "Default")
      (node (ref "D4") (pin "2") (pinfunction "DO_2") (pintype "passive"))
      (node (ref "D5") (pin "4") (pinfunction "DI_4") (pintype "passive"))
    )
    (net (code "32") (name "Net-(D5-DO)") (class "Default")
      (node (ref "D5") (pin "2") (pinfunction "DO_2") (pintype "passive"))
      (node (ref "D6") (pin "4") (pinfunction "DI_4") (pintype "passive"))
    )
    (net (code "33") (name "Net-(D6-DO)") (class "Default")
      (node (ref "D6") (pin "2") (pinfunction "DO_2") (pintype "passive"))
      (node (ref "D7") (pin "4") (pinfunction "DI_4") (pintype "passive"))
    )
    (net (code "34") (name "Net-(P1-Pad1)") (class "Default")
      (node (ref "P1") (pin "1") (pinfunction "1_1") (pintype "passive"))
      (node (ref "S1") (pin "1") (pinfunction "1_1") (pintype "passive"))
    )
    (net (code "35") (name "Net-(P2-Pad2)") (class "Default")
      (node (ref "P2") (pin "2") (pinfunction "2_2") (pintype "passive"))
      (node (ref "R1") (pin "2") (pinfunction "2_2") (pintype "passive"))
    )
    (net (code "36") (name "Net-(Q1-D)") (class "Default")
      (node (ref "C36") (pin "2") (pinfunction "2_2") (pintype "passive"))
      (node (ref "M1") (pin "2") (pinfunction "2_2") (pintype "passive"))
      (node (ref "Q1") (pin "3") (pinfunction "D_3") (pintype "passive"))
    )
    (net (code "37") (name "Net-(Q1-G)") (class "Default")
      (node (ref "Q1") (pin "1") (pinfunction "G_1") (pintype "passive"))
      (node (ref "R12") (pin "2") (pinfunction "2_2") (pintype "passive"))
      (node (ref "R13") (pin "2") (pinfunction "2_2") (pintype "passive"))
    )
    (net (code "38") (name "Net-(Q2-D)") (class "Default")
      (node (ref "C37") (pin "2") (pinfunction "2_2") (pintype "passive"))
      (node (ref "M2") (pin "2") (pinfunction "2_2") (pintype "passive"))
      (node (ref "Q2") (pin "3") (pinfunction "D_3") (pintype "passive"))
    )
    (net (code "39") (name "Net-(Q2-G)") (class "Default")
      (node (ref "Q2") (pin "1") (pinfunction "G_1") (pintype "passive"))
      (node (ref "R14") (pin "2") (pinfunction "2_2") (pintype "passive"))
      (node (ref "R15") (pin "2") (pinfunction "2_2") (pintype "passive"))
    )
    (net (code "40") (name "Net-(Q3-D)") (class "Default")
      (node (ref "C38") (pin "2") (pinfunction "2_2") (pintype "passive"))
      (node (ref "M3") (pin "2") (pinfunction "2_2") (pintype "passive"))
      (node (ref "Q3") (pin "3") (pinfunction "D_3") (pintype "passive"))
    )
    (net (code "41") (name "Net-(Q3-G)") (class "Default")
      (node (ref "Q3") (pin "1") (pinfunction "G_1") (pintype "passive"))
      (node (ref "R16") (pin "2") (pinfunction "2_2") (pintype "passive"))
      (node (ref "R17") (pin "2") (pinfunction "2_2") (pintype "passive"))
    )
    (net (code "42") (name "Net-(Q4-D)") (class "Default")
      (node (ref "C39") (pin "2") (pinfunction "2_2") (pintype "passive"))
      (node (ref "M4") (pin "2") (pinfunction "2_2") (pintype "passive"))
      (node (ref "Q4") (pin "3") (pinfunction "D_3") (pintype "passive"))
    )
    (net (code "43") (name "Net-(Q4-G)") (class "Default")
      (node (ref "Q4") (pin "1") (pinfunction "G_1") (pintype "passive"))
      (node (ref "R18") (pin "2") (pinfunction "2_2") (pintype "passive"))
      (node (ref "R19") (pin "2") (pinfunction "2_2") (pintype "passive"))
    )
    (net (code "44") (name "Net-(U1-OSC_IN{slash}PD0)") (class "Default")
      (node (ref "U1") (pin "5") (pinfunction "OSC_IN/PD0_5") (pintype "input"))
      (node (ref "Y1") (pin "3") (pinfunction "3_3") (pintype "passive"))
    )
    (net (code "45") (name "Net-(U1-OSC_OUT{slash}PD1)") (class "Default")
      (node (ref "U1") (pin "6") (pinfunction "OSC_OUT/PD1_6") (pintype "output"))
      (node (ref "Y1") (pin "1") (pinfunction "1_1") (pintype "passive"))
    )
    (net (code "46") (name "Net-(U1-PB2{slash}BOOT1)") (class "Default")
      (node (ref "R21") (pin "1") (pinfunction "1_1") (pintype "passive"))
      (node (ref "U1") (pin "20") (pinfunction "PB2/BOOT1_20") (pintype "bidirectional"))
    )
    (net (code "47") (name "Net-(U2-C+)") (class "Default")
      (node (ref "C2") (pin "1") (pinfunction "1_1") (pintype "passive"))
      (node (ref "U2") (pin "6") (pinfunction "C+_6") (pintype "passive"))
    )
    (net (code "48") (name "Net-(U2-C-)") (class "Default")
      (node (ref "C2") (pin "2") (pinfunction "2_2") (pintype "passive"))
      (node (ref "U2") (pin "4") (pinfunction "C-_4") (pintype "passive"))
    )
    (net (code "49") (name "Net-(U4-CPOUT)") (class "Default")
      (node (ref "C32") (pin "2") (pinfunction "2_2") (pintype "passive"))
      (node (ref "U4") (pin "20") (pinfunction "CPOUT_20") (pintype "passive"))
    )
    (net (code "50") (name "Net-(U4-FSYNC)") (class "Default")
      (node (ref "R20") (pin "2") (pinfunction "2_2") (pintype "passive"))
      (node (ref "U4") (pin "11") (pinfunction "FSYNC_11") (pintype "passive"))
    )
    (net (code "51") (name "Net-(U4-REGOUT)") (class "Default")
      (node (ref "C35") (pin "1") (pinfunction "1_1") (pintype "passive"))
      (node (ref "U4") (pin "10") (pinfunction "REGOUT_10") (pintype "passive"))
    )
    (net (code "52") (name "Net-(U6-ANT1)") (class "Default")
      (node (ref "L2") (pin "2") (pinfunction "2_2") (pintype "passive"))
      (node (ref "L3") (pin "2") (pinfunction "2_2") (pintype "passive"))
      (node (ref "U6") (pin "12") (pinfunction "ANT1_12") (pintype "passive"))
    )
    (net (code "53") (name "Net-(U6-ANT2)") (class "Default")
      (node (ref "L2") (pin "1") (pinfunction "1_1") (pintype "passive"))
      (node (ref "L4") (pin "1") (pinfunction "1_1") (pintype "passive"))
      (node (ref "U6") (pin "13") (pinfunction "ANT2_13") (pintype "passive"))
    )
    (net (code "54") (name "Net-(U6-DVDD)") (class "Default")
      (node (ref "C24") (pin "1") (pinfunction "1_1") (pintype "passive"))
      (node (ref "U6") (pin "19") (pinfunction "DVDD_19") (pintype "passive"))
    )
    (net (code "55") (name "Net-(U6-IREF)") (class "Default")
      (node (ref "R22") (pin "2") (pinfunction "2_2") (pintype "passive"))
      (node (ref "U6") (pin "16") (pinfunction "IREF_16") (pintype "passive"))
    )
    (net (code "56") (name "Net-(U6-VDD_PA)") (class "Default")
      (node (ref "C26") (pin "1") (pinfunction "1_1") (pintype "passive"))
      (node (ref "C27") (pin "1") (pinfunction "1_1") (pintype "passive"))
      (node (ref "L3") (pin "1") (pinfunction "1_1") (pintype "passive"))
      (node (ref "U6") (pin "11") (pinfunction "VDD_PA_11") (pintype "passive"))
    )
    (net (code "57") (name "Net-(U6-XC1)") (class "Default")
      (node (ref "C30") (pin "2") (pinfunction "2_2") (pintype "passive"))
      (node (ref "U6") (pin "10") (pinfunction "XC1_10") (pintype "passive"))
      (node (ref "X2") (pin "3") (pinfunction "3_3") (pintype "passive"))
    )
    (net (code "58") (name "Net-(U6-XC2)") (class "Default")
      (node (ref "C29") (pin "2") (pinfunction "2_2") (pintype "passive"))
      (node (ref "U6") (pin "9") (pinfunction "XC2_9") (pintype "passive"))
      (node (ref "X2") (pin "1") (pinfunction "1_1") (pintype "passive"))
    )
    (net (code "59") (name "RF_3.3V") (class "Default")
      (node (ref "C22") (pin "2") (pinfunction "2_2") (pintype "passive"))
      (node (ref "C23") (pin "2") (pinfunction "2_2") (pintype "passive"))
      (node (ref "R9") (pin "1") (pinfunction "1_1") (pintype "passive"))
      (node (ref "U6") (pin "15") (pinfunction "VDD_15") (pintype "passive"))
      (node (ref "U6") (pin "18") (pinfunction "VDD_18") (pintype "passive"))
      (node (ref "U6") (pin "7") (pinfunction "VDD_7") (pintype "passive"))
    )
    (net (code "60") (name "RF_GND") (class "Default")
      (node (ref "C22") (pin "1") (pinfunction "1_1") (pintype "passive"))
      (node (ref "C23") (pin "1") (pinfunction "1_1") (pintype "passive"))
      (node (ref "C24") (pin "2") (pinfunction "2_2") (pintype "passive"))
      (node (ref "C26") (pin "2") (pinfunction "2_2") (pintype "passive"))
      (node (ref "C27") (pin "2") (pinfunction "2_2") (pintype "passive"))
      (node (ref "C28") (pin "1") (pinfunction "1_1") (pintype "passive"))
      (node (ref "C29") (pin "1") (pinfunction "1_1") (pintype "passive"))
      (node (ref "C30") (pin "1") (pinfunction "1_1") (pintype "passive"))
      (node (ref "R22") (pin "1") (pinfunction "1_1") (pintype "passive"))
      (node (ref "R8") (pin "1") (pinfunction "1_1") (pintype "passive"))
      (node (ref "U6") (pin "14") (pinfunction "VSS_14") (pintype "passive"))
      (node (ref "U6") (pin "17") (pinfunction "VSS_17") (pintype "passive"))
      (node (ref "U6") (pin "20") (pinfunction "VSS_20") (pintype "passive"))
      (node (ref "U6") (pin "8") (pinfunction "VSS_8") (pintype "passive"))
    )
    (net (code "61") (name "VBAT") (class "Default")
      (node (ref "C1") (pin "2") (pinfunction "2_2") (pintype "passive"))
      (node (ref "C36") (pin "1") (pinfunction "1_1") (pintype "passive"))
      (node (ref "C37") (pin "1") (pinfunction "1_1") (pintype "passive"))
      (node (ref "C38") (pin "1") (pinfunction "1_1") (pintype "passive"))
      (node (ref "C39") (pin "1") (pinfunction "1_1") (pintype "passive"))
      (node (ref "M1") (pin "1") (pinfunction "1_1") (pintype "passive"))
      (node (ref "M2") (pin "1") (pinfunction "1_1") (pintype "passive"))
      (node (ref "M3") (pin "1") (pinfunction "1_1") (pintype "passive"))
      (node (ref "M4") (pin "1") (pinfunction "1_1") (pintype "passive"))
      (node (ref "R6") (pin "1") (pinfunction "1_1") (pintype "passive"))
      (node (ref "S1") (pin "2") (pinfunction "2_2") (pintype "passive"))
      (node (ref "U2") (pin "3") (pinfunction "EN_3") (pintype "passive"))
      (node (ref "U2") (pin "5") (pinfunction "VIN_5") (pintype "passive"))
    )
    (net (code "62") (name "unconnected-(D7-DO-Pad2)") (class "Default")
      (node (ref "D7") (pin "2") (pinfunction "DO_2") (pintype "passive"))
    )
    (net (code "63") (name "unconnected-(S1-Pad3)") (class "Default")
      (node (ref "S1") (pin "3") (pinfunction "3_3") (pintype "passive+no_connect"))
    )
    (net (code "64") (name "unconnected-(U1-PA0-WKUP-Pad10)") (class "Default")
      (node (ref "U1") (pin "10") (pinfunction "PA0-WKUP_10") (pintype "bidirectional"))
    )
    (net (code "65") (name "unconnected-(U1-PA2-Pad12)") (class "Default")
      (node (ref "U1") (pin "12") (pinfunction "PA2_12") (pintype "bidirectional"))
    )
    (net (code "66") (name "unconnected-(U1-PA5-Pad15)") (class "Default")
      (node (ref "U1") (pin "15") (pinfunction "PA5_15") (pintype "bidirectional"))
    )
    (net (code "67") (name "unconnected-(U1-PA8-Pad29)") (class "Default")
      (node (ref "U1") (pin "29") (pinfunction "PA8_29") (pintype "bidirectional"))
    )
    (net (code "68") (name "unconnected-(U1-PA15{slash}JTDI-Pad38)") (class "Default")
      (node (ref "U1") (pin "38") (pinfunction "PA15/JTDI_38") (pintype "bidirectional"))
    )
    (net (code "69") (name "unconnected-(U1-PB4{slash}JNTRST-Pad40)") (class "Default")
      (node (ref "U1") (pin "40") (pinfunction "PB4/JNTRST_40") (pintype "bidirectional"))
    )
    (net (code "70") (name "unconnected-(U1-PB5-Pad41)") (class "Default")
      (node (ref "U1") (pin "41") (pinfunction "PB5_41") (pintype "bidirectional"))
    )
    (net (code "71") (name "unconnected-(U1-PB8-Pad45)") (class "Default")
      (node (ref "U1") (pin "45") (pinfunction "PB8_45") (pintype "bidirectional"))
    )
    (net (code "72") (name "unconnected-(U1-PB9-Pad46)") (class "Default")
      (node (ref "U1") (pin "46") (pinfunction "PB9_46") (pintype "bidirectional"))
    )
    (net (code "73") (name "unconnected-(U1-PB10-Pad21)") (class "Default")
      (node (ref "U1") (pin "21") (pinfunction "PB10_21") (pintype "bidirectional"))
    )
    (net (code "74") (name "unconnected-(U1-PB11-Pad22)") (class "Default")
      (node (ref "U1") (pin "22") (pinfunction "PB11_22") (pintype "bidirectional"))
    )
    (net (code "75") (name "unconnected-(U1-PC13-TAMPER-RTC-Pad2)") (class "Default")
      (node (ref "U1") (pin "2") (pinfunction "PC13-TAMPER-RTC_2") (pintype "bidirectional"))
    )
    (net (code "76") (name "unconnected-(U1-PC14-OSC32_IN-Pad3)") (class "Default")
      (node (ref "U1") (pin "3") (pinfunction "PC14-OSC32_IN_3") (pintype "bidirectional"))
    )
    (net (code "77") (name "unconnected-(U1-PC15-OSC32_OUT-Pad4)") (class "Default")
      (node (ref "U1") (pin "4") (pinfunction "PC15-OSC32_OUT_4") (pintype "bidirectional"))
    )
    (net (code "78") (name "unconnected-(U4-A-CL-Pad7)") (class "Default")
      (node (ref "U4") (pin "7") (pinfunction "A-CL_7") (pintype "passive+no_connect"))
    )
    (net (code "79") (name "unconnected-(U4-A_DA-Pad6)") (class "Default")
      (node (ref "U4") (pin "6") (pinfunction "A_DA_6") (pintype "passive+no_connect"))
    )
    (net (code "80") (name "unconnected-(U4-CLKOUT-Pad22)") (class "Default")
      (node (ref "U4") (pin "22") (pinfunction "CLKOUT_22") (pintype "passive+no_connect"))
    )
    (net (code "81") (name "unconnected-(U4-NC-Pad2)") (class "Default")
      (node (ref "U4") (pin "2") (pinfunction "NC_2") (pintype "passive+no_connect"))
    )
    (net (code "82") (name "unconnected-(U4-NC-Pad3)") (class "Default")
      (node (ref "U4") (pin "3") (pinfunction "NC_3") (pintype "passive+no_connect"))
    )
    (net (code "83") (name "unconnected-(U4-NC-Pad4)") (class "Default")
      (node (ref "U4") (pin "4") (pinfunction "NC_4") (pintype "passive+no_connect"))
    )
    (net (code "84") (name "unconnected-(U4-NC-Pad5)") (class "Default")
      (node (ref "U4") (pin "5") (pinfunction "NC_5") (pintype "passive+no_connect"))
    )
    (net (code "85") (name "unconnected-(U4-NC-Pad14)") (class "Default")
      (node (ref "U4") (pin "14") (pinfunction "NC_14") (pintype "passive+no_connect"))
    )
    (net (code "86") (name "unconnected-(U4-NC-Pad15)") (class "Default")
      (node (ref "U4") (pin "15") (pinfunction "NC_15") (pintype "passive+no_connect"))
    )
    (net (code "87") (name "unconnected-(U4-NC-Pad16)") (class "Default")
      (node (ref "U4") (pin "16") (pinfunction "NC_16") (pintype "passive+no_connect"))
    )
    (net (code "88") (name "unconnected-(U4-NC-Pad17)") (class "Default")
      (node (ref "U4") (pin "17") (pinfunction "NC_17") (pintype "passive+no_connect"))
    )
    (net (code "89") (name "unconnected-(U4-RESV-Pad19)") (class "Default")
      (node (ref "U4") (pin "19") (pinfunction "RESV_19") (pintype "passive+no_connect"))
    )
    (net (code "90") (name "unconnected-(U4-RESV-Pad21)") (class "Default")
      (node (ref "U4") (pin "21") (pinfunction "RESV_21") (pintype "passive+no_connect"))
    )
    (net (code "91") (name "unconnected-(X2-GND-Pad2)") (class "Default")
      (node (ref "X2") (pin "2") (pinfunction "GND_2") (pintype "passive+no_connect"))
    )
    (net (code "92") (name "unconnected-(X2-GND-Pad4)") (class "Default")
      (node (ref "X2") (pin "4") (pinfunction "GND_4") (pintype "passive+no_connect"))
    )
  )
)
